# ROMS.net
KiCad netlist of a schematic drawn in EAGLE
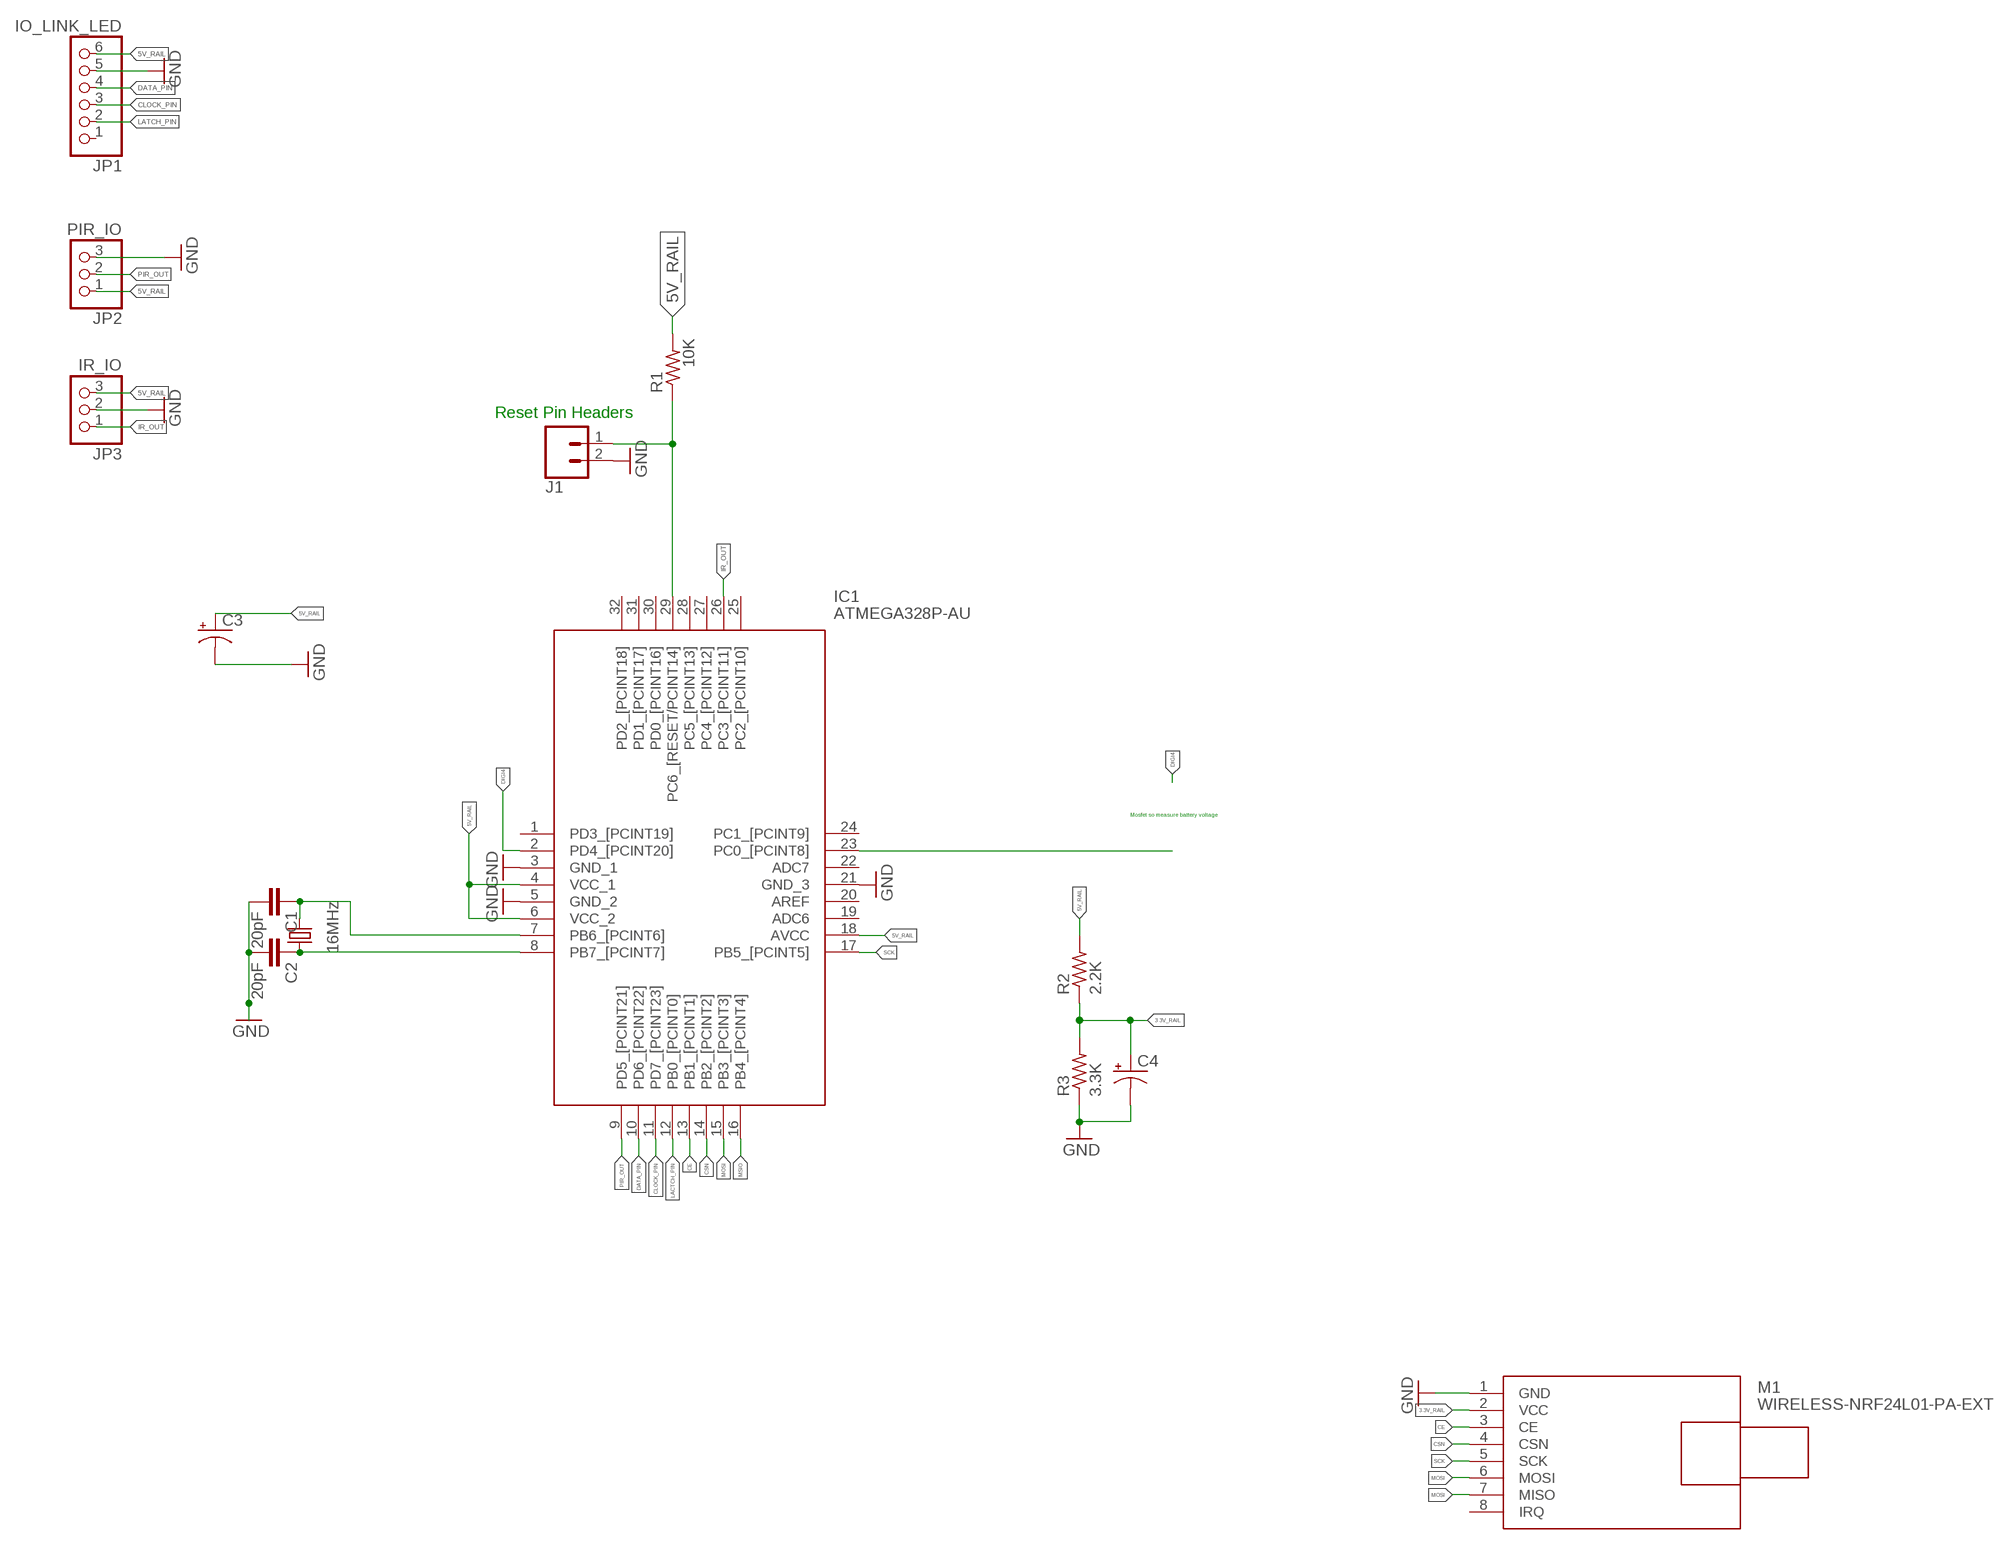
[diagram p0: schematic, sheet 1]

(export (version "E")
  (design (tool "Eeschema 10.0.6"))
  (components
    (comp (ref "C1")
      (value "20pF")
      (footprint "eagle-import:0402-TIGHT")
      (libsource (lib "eagle-import") (part "20PF-0402T-50V-5%"))
    )
    (comp (ref "C2")
      (value "20pF")
      (footprint "eagle-import:0402-TIGHT")
      (libsource (lib "eagle-import") (part "20PF-0402T-50V-5%"))
    )
    (comp (ref "C3")
      (value "CPOL-USTT2D5")
      (footprint "eagle-import:TT2D5")
      (libsource (lib "eagle-import") (part "CPOL-USTT2D5"))
    )
    (comp (ref "C4")
      (value "CPOL-USTT2D5")
      (footprint "eagle-import:TT2D5")
      (libsource (lib "eagle-import") (part "CPOL-USTT2D5"))
    )
    (comp (ref "IC1")
      (value "ATMEGA328P-AU")
      (footprint "eagle-import:QFP80P900X900X120-32N")
      (fields
        (field (name "MOUSER_PART_NUMBER") "556-ATMEGA328P-AU")
        (field (name "RS_PART_NUMBER") "1310271P")
      )
      (libsource (lib "eagle-import") (part "ATMEGA328P-AU"))
    )
    (comp (ref "J1")
      (value "CONN_02")
      (footprint "eagle-import:1X02")
      (libsource (lib "eagle-import") (part "CONN_02"))
    )
    (comp (ref "JP1")
      (value "IO_LINK_LED")
      (footprint "eagle-import:1X06")
      (libsource (lib "eagle-import") (part "PINHD-1X6"))
    )
    (comp (ref "JP2")
      (value "PIR_IO")
      (footprint "eagle-import:1X03")
      (libsource (lib "eagle-import") (part "PINHD-1X3"))
    )
    (comp (ref "JP3")
      (value "IR_IO")
      (footprint "eagle-import:1X03")
      (libsource (lib "eagle-import") (part "PINHD-1X3"))
    )
    (comp (ref "M1")
      (value "WIRELESS-NRF24L01-PA-EXT")
      (footprint "eagle-import:WIRELESS-NRD24L01-PA-EXT")
      (libsource (lib "eagle-import") (part "WIRELESS-NRF24L01-PA-EXT"))
    )
    (comp (ref "R1")
      (value "10K")
      (footprint "eagle-import:0207_10")
      (libsource (lib "eagle-import") (part "R-US_0207/10"))
    )
    (comp (ref "R2")
      (value "2.2K")
      (footprint "eagle-import:0805-THM")
      (libsource (lib "eagle-import") (part "FLIPFLOP-RES"))
    )
    (comp (ref "R3")
      (value "3.3K")
      (footprint "eagle-import:0805-THM")
      (libsource (lib "eagle-import") (part "FLIPFLOP-RES"))
    )
    (comp (ref "Y1")
      (value "16MHz")
      (footprint "eagle-import:HC49US")
      (libsource (lib "eagle-import") (part "CRYSTAL-16MHZPTH-HC49US"))
    )
  )
  (nets
    (net (code "1") (name "3.3V_RAIL") (class "Default")
      (node (ref "C4") (pin "+") (pinfunction "+_+") (pintype "passive"))
      (node (ref "M1") (pin "2") (pinfunction "VCC_2") (pintype "power_in"))
      (node (ref "R2") (pin "1") (pinfunction "1_1") (pintype "passive"))
      (node (ref "R3") (pin "2") (pinfunction "2_2") (pintype "passive"))
    )
    (net (code "2") (name "5V_RAIL") (class "Default")
      (node (ref "C3") (pin "+") (pinfunction "+_+") (pintype "passive"))
      (node (ref "IC1") (pin "18") (pinfunction "AVCC_18") (pintype "power_in"))
      (node (ref "IC1") (pin "4") (pinfunction "VCC_1_4") (pintype "power_in"))
      (node (ref "IC1") (pin "6") (pinfunction "VCC_2_6") (pintype "power_in"))
      (node (ref "JP1") (pin "6") (pinfunction "6_6") (pintype "passive"))
      (node (ref "JP2") (pin "1") (pinfunction "1_1") (pintype "passive"))
      (node (ref "JP3") (pin "3") (pinfunction "3_3") (pintype "passive"))
      (node (ref "R1") (pin "2") (pinfunction "2_2") (pintype "passive"))
      (node (ref "R2") (pin "2") (pinfunction "2_2") (pintype "passive"))
    )
    (net (code "3") (name "CE") (class "Default")
      (node (ref "IC1") (pin "13") (pinfunction "PB1_[PCINT1]_13") (pintype "bidirectional"))
      (node (ref "M1") (pin "3") (pinfunction "CE_3") (pintype "bidirectional"))
    )
    (net (code "4") (name "CLOCK_PIN") (class "Default")
      (node (ref "IC1") (pin "11") (pinfunction "PD7_[PCINT23]_11") (pintype "bidirectional"))
      (node (ref "JP1") (pin "3") (pinfunction "3_3") (pintype "passive"))
    )
    (net (code "5") (name "CSN") (class "Default")
      (node (ref "IC1") (pin "14") (pinfunction "PB2_[PCINT2]_14") (pintype "bidirectional"))
      (node (ref "M1") (pin "4") (pinfunction "CSN_4") (pintype "bidirectional"))
    )
    (net (code "6") (name "DATA_PIN") (class "Default")
      (node (ref "IC1") (pin "10") (pinfunction "PD6_[PCINT22]_10") (pintype "bidirectional"))
      (node (ref "JP1") (pin "4") (pinfunction "4_4") (pintype "passive"))
    )
    (net (code "7") (name "DIGI4") (class "Default")
      (node (ref "IC1") (pin "2") (pinfunction "PD4_[PCINT20]_2") (pintype "bidirectional"))
    )
    (net (code "8") (name "GND") (class "Default")
      (node (ref "C1") (pin "2") (pinfunction "2_2") (pintype "passive"))
      (node (ref "C2") (pin "2") (pinfunction "2_2") (pintype "passive"))
      (node (ref "C3") (pin "-") (pinfunction "-_-") (pintype "passive"))
      (node (ref "C4") (pin "-") (pinfunction "-_-") (pintype "passive"))
      (node (ref "IC1") (pin "21") (pinfunction "GND_3_21") (pintype "power_in"))
      (node (ref "IC1") (pin "3") (pinfunction "GND_1_3") (pintype "power_in"))
      (node (ref "IC1") (pin "5") (pinfunction "GND_2_5") (pintype "power_in"))
      (node (ref "J1") (pin "2") (pinfunction "2_2") (pintype "passive"))
      (node (ref "JP1") (pin "5") (pinfunction "5_5") (pintype "passive"))
      (node (ref "JP2") (pin "3") (pinfunction "3_3") (pintype "passive"))
      (node (ref "JP3") (pin "2") (pinfunction "2_2") (pintype "passive"))
      (node (ref "M1") (pin "1") (pinfunction "GND_1") (pintype "power_in"))
      (node (ref "R3") (pin "1") (pinfunction "1_1") (pintype "passive"))
    )
    (net (code "9") (name "IR_OUT") (class "Default")
      (node (ref "IC1") (pin "26") (pinfunction "PC3_[PCINT11]_26") (pintype "bidirectional"))
      (node (ref "JP3") (pin "1") (pinfunction "1_1") (pintype "passive"))
    )
    (net (code "10") (name "LACTCH_PIN") (class "Default")
      (node (ref "IC1") (pin "12") (pinfunction "PB0_[PCINT0]_12") (pintype "bidirectional"))
    )
    (net (code "11") (name "LATCH_PIN") (class "Default")
      (node (ref "JP1") (pin "2") (pinfunction "2_2") (pintype "passive"))
    )
    (net (code "12") (name "MOSI") (class "Default")
      (node (ref "IC1") (pin "15") (pinfunction "PB3_[PCINT3]_15") (pintype "bidirectional"))
      (node (ref "M1") (pin "6") (pinfunction "MOSI_6") (pintype "bidirectional"))
      (node (ref "M1") (pin "7") (pinfunction "MISO_7") (pintype "bidirectional"))
    )
    (net (code "13") (name "MSIO") (class "Default")
      (node (ref "IC1") (pin "16") (pinfunction "PB4_[PCINT4]_16") (pintype "bidirectional"))
    )
    (net (code "14") (name "Net-(IC1-PB6_[PCINT6])") (class "Default")
      (node (ref "C1") (pin "1") (pinfunction "1_1") (pintype "passive"))
      (node (ref "IC1") (pin "7") (pinfunction "PB6_[PCINT6]_7") (pintype "bidirectional"))
      (node (ref "Y1") (pin "2") (pinfunction "2_2") (pintype "passive"))
    )
    (net (code "15") (name "Net-(IC1-PB7_[PCINT7])") (class "Default")
      (node (ref "C2") (pin "1") (pinfunction "1_1") (pintype "passive"))
      (node (ref "IC1") (pin "8") (pinfunction "PB7_[PCINT7]_8") (pintype "bidirectional"))
      (node (ref "Y1") (pin "1") (pinfunction "1_1") (pintype "passive"))
    )
    (net (code "16") (name "Net-(IC1-PC6_[RESET{slash}PCINT14])") (class "Default")
      (node (ref "IC1") (pin "29") (pinfunction "PC6_[RESET/PCINT14]_29") (pintype "bidirectional"))
      (node (ref "J1") (pin "1") (pinfunction "1_1") (pintype "passive"))
      (node (ref "R1") (pin "1") (pinfunction "1_1") (pintype "passive"))
    )
    (net (code "17") (name "PIR_OUT") (class "Default")
      (node (ref "IC1") (pin "9") (pinfunction "PD5_[PCINT21]_9") (pintype "bidirectional"))
      (node (ref "JP2") (pin "2") (pinfunction "2_2") (pintype "passive"))
    )
    (net (code "18") (name "SCK") (class "Default")
      (node (ref "IC1") (pin "17") (pinfunction "PB5_[PCINT5]_17") (pintype "bidirectional"))
      (node (ref "M1") (pin "5") (pinfunction "SCK_5") (pintype "bidirectional"))
    )
    (net (code "19") (name "unconnected-(IC1-ADC6-Pad19)") (class "Default")
      (node (ref "IC1") (pin "19") (pinfunction "ADC6_19") (pintype "bidirectional"))
    )
    (net (code "20") (name "unconnected-(IC1-ADC7-Pad22)") (class "Default")
      (node (ref "IC1") (pin "22") (pinfunction "ADC7_22") (pintype "bidirectional"))
    )
    (net (code "21") (name "unconnected-(IC1-AREF-Pad20)") (class "Default")
      (node (ref "IC1") (pin "20") (pinfunction "AREF_20") (pintype "bidirectional"))
    )
    (net (code "22") (name "unconnected-(IC1-PC0_[PCINT8]-Pad23)") (class "Default")
      (node (ref "IC1") (pin "23") (pinfunction "PC0_[PCINT8]_23") (pintype "bidirectional"))
    )
    (net (code "23") (name "unconnected-(IC1-PC1_[PCINT9]-Pad24)") (class "Default")
      (node (ref "IC1") (pin "24") (pinfunction "PC1_[PCINT9]_24") (pintype "bidirectional"))
    )
    (net (code "24") (name "unconnected-(IC1-PC2_[PCINT10]-Pad25)") (class "Default")
      (node (ref "IC1") (pin "25") (pinfunction "PC2_[PCINT10]_25") (pintype "bidirectional"))
    )
    (net (code "25") (name "unconnected-(IC1-PC4_[PCINT12]-Pad27)") (class "Default")
      (node (ref "IC1") (pin "27") (pinfunction "PC4_[PCINT12]_27") (pintype "bidirectional"))
    )
    (net (code "26") (name "unconnected-(IC1-PC5_[PCINT13]-Pad28)") (class "Default")
      (node (ref "IC1") (pin "28") (pinfunction "PC5_[PCINT13]_28") (pintype "bidirectional"))
    )
    (net (code "27") (name "unconnected-(IC1-PD0_[PCINT16]-Pad30)") (class "Default")
      (node (ref "IC1") (pin "30") (pinfunction "PD0_[PCINT16]_30") (pintype "bidirectional"))
    )
    (net (code "28") (name "unconnected-(IC1-PD1_[PCINT17]-Pad31)") (class "Default")
      (node (ref "IC1") (pin "31") (pinfunction "PD1_[PCINT17]_31") (pintype "bidirectional"))
    )
    (net (code "29") (name "unconnected-(IC1-PD2_[PCINT18]-Pad32)") (class "Default")
      (node (ref "IC1") (pin "32") (pinfunction "PD2_[PCINT18]_32") (pintype "bidirectional"))
    )
    (net (code "30") (name "unconnected-(IC1-PD3_[PCINT19]-Pad1)") (class "Default")
      (node (ref "IC1") (pin "1") (pinfunction "PD3_[PCINT19]_1") (pintype "bidirectional"))
    )
    (net (code "31") (name "unconnected-(JP1-Pad1)") (class "Default")
      (node (ref "JP1") (pin "1") (pinfunction "1_1") (pintype "passive"))
    )
    (net (code "32") (name "unconnected-(M1-IRQ-Pad8)") (class "Default")
      (node (ref "M1") (pin "8") (pinfunction "IRQ_8") (pintype "bidirectional"))
    )
  )
)
